# Inputs.net
KiCad netlist of a schematic drawn in Altium Designer
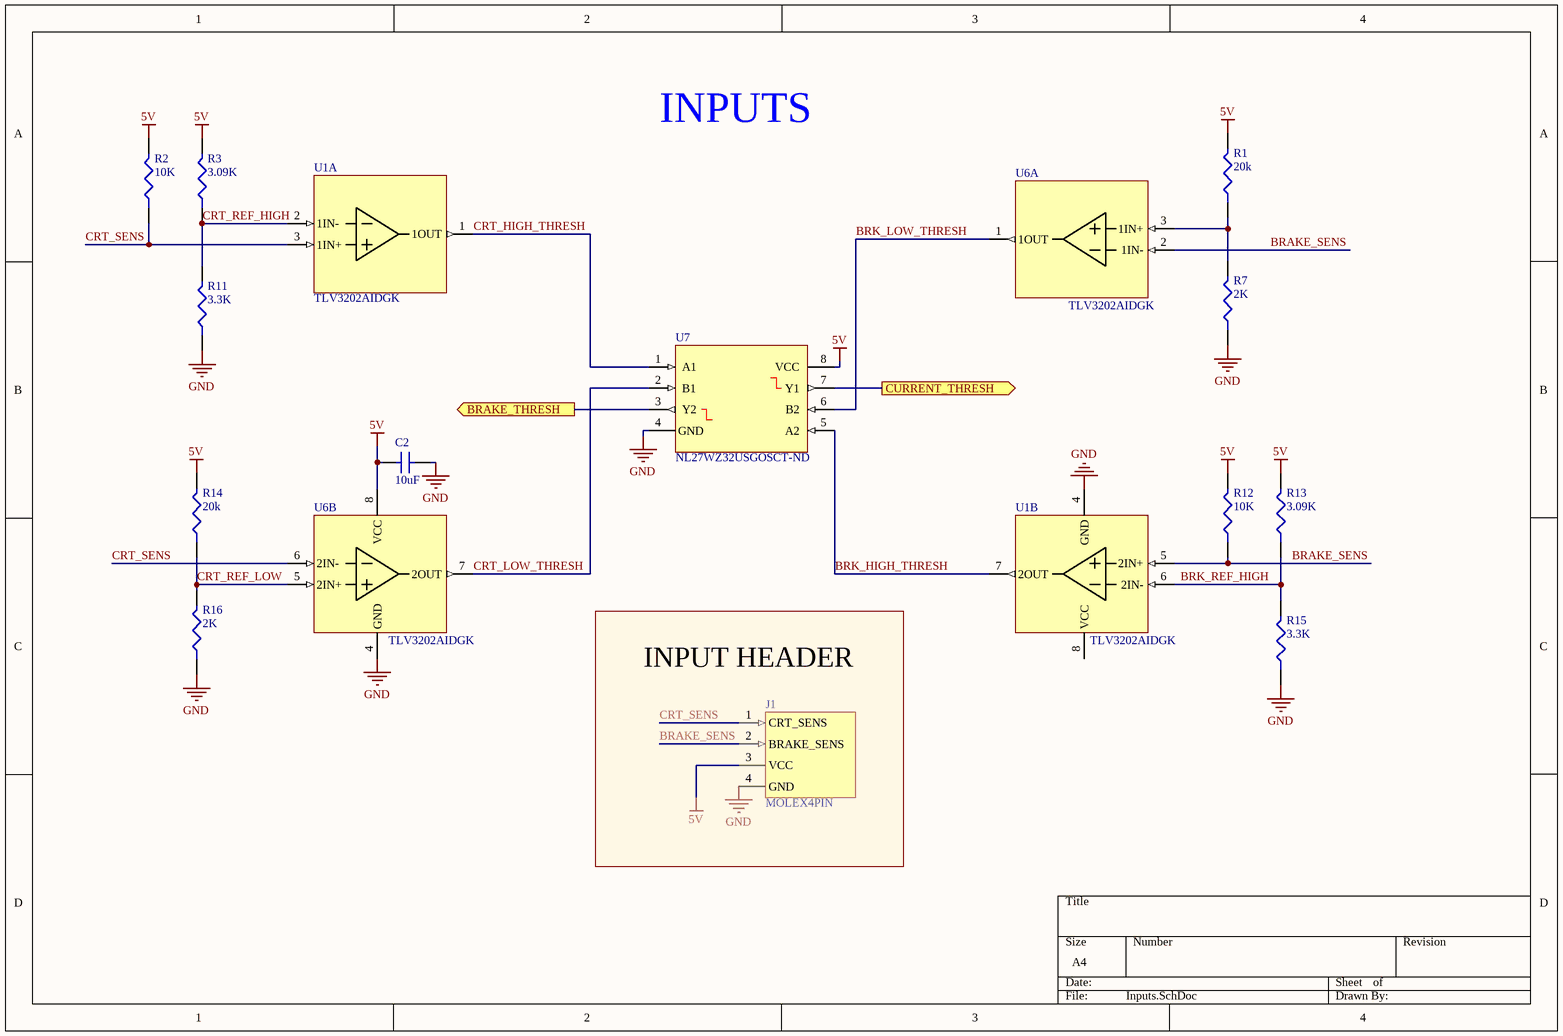
[diagram p0: Inputs.SchDoc]

(export (version "E")
  (design (tool "Eeschema 10.0.6"))
  (components
    (comp (ref "C2")
      (value "10uF")
      (footprint "C0805")
      (description "Cap Ceramic 10uF 10V X5R 10% SMD 0805 85C Embossed T/R")
      (fields
        (field (name "MANUFACTURER") "Samsung")
        (field (name "MANUFACTURER PART NUMBER") "CL21A106KPFNNNG")
      )
      (libsource (lib "BSPD") (part "CL21A106KPFNNNG"))
    )
    (comp (ref "J1")
      (value "MOLEX4PIN")
      (footprint "MOLEX_4PIN")
      (fields (field (name "MANUFACTURER") "Molex") (field (name "MANUFACTURER PART NUMBER") "43650-0400"))
      (libsource (lib "BSPD") (part "43650-0400"))
    )
    (comp (ref "R1")
      (value "20k")
      (footprint "RESC1608X06N")
      (fields
        (field (name "MANUFACTURER") "Yageo")
        (field (name "MANUFACTURER PART NUMBER") "RC0603FR-0722KL")
        (field (name "TOLERANCE") "1%")
      )
      (libsource (lib "BSPD") (part "RC0603FR-0722KL"))
    )
    (comp (ref "R2")
      (value "10K")
      (footprint "R0805")
      (description "RES SMD 10K OHM 0.1% 1/8W 0805")
      (fields
        (field (name "MANUFACTURER") "Panasonic")
        (field (name "MANUFACTURER PART NUMBER") "ERA6AEB103V")
      )
      (libsource (lib "BSPD") (part "ERA6AEB103V"))
    )
    (comp (ref "R3")
      (value "3.09K")
      (footprint "ERJPB3")
      (description "RES SMD 3.09K OHM 0.1% 1/5W 0603")
      (fields
        (field (name "MANUFACTURER") "Panasonic")
        (field (name "MANUFACTURER PART NUMBER") "ERJ-PB3B3091V")
      )
      (libsource (lib "BSPD") (part "ERJ-PB3B3091V"))
    )
    (comp (ref "R7")
      (value "2K")
      (footprint "R0805")
      (description "RES SMD 2K OHM 0.1% 1/8W 0805")
      (fields
        (field (name "MANUFACTURER") "Panasonic")
        (field (name "MANUFACTURER PART NUMBER") "ERA6AEB202V")
      )
      (libsource (lib "BSPD") (part "ERA6AEB202V"))
    )
    (comp (ref "R11")
      (value "3.3K")
      (footprint "ERJPB3")
      (description "RES SMD 3.3K OHM 0.1% 1/5W 0603")
      (fields
        (field (name "MANUFACTURER") "Panasonic")
        (field (name "MANUFACTURER PART NUMBER") "ERJ-PB3B3301V")
      )
      (libsource (lib "BSPD") (part "ERJ-PB3B3301V"))
    )
    (comp (ref "R12")
      (value "10K")
      (footprint "R0805")
      (description "RES SMD 10K OHM 0.1% 1/8W 0805")
      (fields
        (field (name "MANUFACTURER") "Panasonic")
        (field (name "MANUFACTURER PART NUMBER") "ERA6AEB103V")
      )
      (libsource (lib "BSPD") (part "ERA6AEB103V"))
    )
    (comp (ref "R13")
      (value "3.09K")
      (footprint "ERJPB3")
      (description "RES SMD 3.09K OHM 0.1% 1/5W 0603")
      (fields
        (field (name "MANUFACTURER") "Panasonic")
        (field (name "MANUFACTURER PART NUMBER") "ERJ-PB3B3091V")
      )
      (libsource (lib "BSPD") (part "ERJ-PB3B3091V"))
    )
    (comp (ref "R14")
      (value "20k")
      (footprint "RESC1608X06N")
      (fields
        (field (name "MANUFACTURER") "Yageo")
        (field (name "MANUFACTURER PART NUMBER") "RC0603FR-0722KL")
        (field (name "TOLERANCE") "1%")
      )
      (libsource (lib "BSPD") (part "RC0603FR-0722KL"))
    )
    (comp (ref "R15")
      (value "3.3K")
      (footprint "ERJPB3")
      (description "RES SMD 3.3K OHM 0.1% 1/5W 0603")
      (fields
        (field (name "MANUFACTURER") "Panasonic")
        (field (name "MANUFACTURER PART NUMBER") "ERJ-PB3B3301V")
      )
      (libsource (lib "BSPD") (part "ERJ-PB3B3301V"))
    )
    (comp (ref "R16")
      (value "2K")
      (footprint "R0805")
      (description "RES SMD 2K OHM 0.1% 1/8W 0805")
      (fields
        (field (name "MANUFACTURER") "Panasonic")
        (field (name "MANUFACTURER PART NUMBER") "ERA6AEB202V")
      )
      (libsource (lib "BSPD") (part "ERA6AEB202V"))
    )
    (comp (ref "U1")
      (value "TLV3202AIDGK")
      (footprint "TLV3202AIDGK")
      (description "IC COMPAR PWR RRI DL PP 8VSSOP")
      (fields (field (name "MANUFACTURER") "Texas Instruments"))
      (libsource (lib "") (part "TLV3202AIDGK_1"))
    )
    (comp (ref "U6")
      (value "TLV3202AIDGK")
      (footprint "TLV3202AIDGK")
      (description "IC COMPAR PWR RRI DL PP 8VSSOP")
      (fields (field (name "MANUFACTURER") "Texas Instruments"))
      (libsource (lib "") (part "TLV3202AIDGK_1"))
    )
    (comp (ref "U7")
      (value "NL27WZ32USGOSCT-ND")
      (footprint "TSSOP50P310X90-8N")
      (description "IC GATE OR 2CH 2-INP US8")
      (fields
        (field (name "MANUFACTURER") "ON Semiconductor")
        (field (name "MANUFACTURER PART NUMBER") "NL27WZ32USG")
      )
      (libsource (lib "BSPD") (part "OR GATE"))
    )
  )
  (nets
    (net (code "1") (name "/BRAKE_SENS") (class "Default")
      (node (ref "J1") (pin "2") (pinfunction "BRAKE_SENS_2") (pintype "input"))
      (node (ref "R12") (pin "1") (pinfunction "1_1") (pintype "passive"))
      (node (ref "U1") (pin "5") (pinfunction "2IN+_5") (pintype "input"))
      (node (ref "U6") (pin "2") (pinfunction "1IN-_2") (pintype "input"))
    )
    (net (code "2") (name "/BRAKE_THRESH") (class "Default")
      (node (ref "U7") (pin "3") (pinfunction "Y2_3") (pintype "output"))
    )
    (net (code "3") (name "/BRK_HIGH_THRESH") (class "Default")
      (node (ref "U1") (pin "7") (pinfunction "2OUT_7") (pintype "output"))
      (node (ref "U7") (pin "5") (pinfunction "A2_5") (pintype "input"))
    )
    (net (code "4") (name "/BRK_LOW_THRESH") (class "Default")
      (node (ref "U6") (pin "1") (pinfunction "1OUT_1") (pintype "output"))
      (node (ref "U7") (pin "6") (pinfunction "B2_6") (pintype "input"))
    )
    (net (code "5") (name "/BRK_REF_HIGH") (class "Default")
      (node (ref "R13") (pin "1") (pinfunction "1_1") (pintype "passive"))
      (node (ref "R15") (pin "2") (pinfunction "2_2") (pintype "passive"))
      (node (ref "U1") (pin "6") (pinfunction "2IN-_6") (pintype "input"))
    )
    (net (code "6") (name "/CRT_HIGH_THRESH") (class "Default")
      (node (ref "U1") (pin "1") (pinfunction "1OUT_1") (pintype "output"))
      (node (ref "U7") (pin "1") (pinfunction "A1_1") (pintype "input"))
    )
    (net (code "7") (name "/CRT_LOW_THRESH") (class "Default")
      (node (ref "U6") (pin "7") (pinfunction "2OUT_7") (pintype "output"))
      (node (ref "U7") (pin "2") (pinfunction "B1_2") (pintype "input"))
    )
    (net (code "8") (name "/CRT_REF_HIGH") (class "Default")
      (node (ref "R11") (pin "2") (pinfunction "2_2") (pintype "passive"))
      (node (ref "R3") (pin "1") (pinfunction "1_1") (pintype "passive"))
      (node (ref "U1") (pin "2") (pinfunction "1IN-_2") (pintype "input"))
    )
    (net (code "9") (name "/CRT_REF_LOW") (class "Default")
      (node (ref "R14") (pin "1") (pinfunction "1_1") (pintype "passive"))
      (node (ref "R16") (pin "2") (pinfunction "2_2") (pintype "passive"))
      (node (ref "U6") (pin "5") (pinfunction "2IN+_5") (pintype "input"))
    )
    (net (code "10") (name "/CRT_SENS") (class "Default")
      (node (ref "J1") (pin "1") (pinfunction "CRT_SENS_1") (pintype "input"))
      (node (ref "R2") (pin "1") (pinfunction "1_1") (pintype "passive"))
      (node (ref "U1") (pin "3") (pinfunction "1IN+_3") (pintype "input"))
      (node (ref "U6") (pin "6") (pinfunction "2IN-_6") (pintype "input"))
    )
    (net (code "11") (name "/CURRENT_THRESH") (class "Default")
      (node (ref "U7") (pin "7") (pinfunction "Y1_7") (pintype "output"))
    )
    (net (code "12") (name "5V") (class "Default")
      (node (ref "C2") (pin "2") (pinfunction "2_2") (pintype "passive"))
      (node (ref "J1") (pin "3") (pinfunction "VCC_3") (pintype "power_in"))
      (node (ref "R1") (pin "2") (pinfunction "2_2") (pintype "passive"))
      (node (ref "R12") (pin "2") (pinfunction "2_2") (pintype "passive"))
      (node (ref "R13") (pin "2") (pinfunction "2_2") (pintype "passive"))
      (node (ref "R14") (pin "2") (pinfunction "2_2") (pintype "passive"))
      (node (ref "R2") (pin "2") (pinfunction "2_2") (pintype "passive"))
      (node (ref "R3") (pin "2") (pinfunction "2_2") (pintype "passive"))
      (node (ref "U6") (pin "8") (pinfunction "VCC_8") (pintype "power_in"))
      (node (ref "U7") (pin "8") (pinfunction "VCC_8") (pintype "power_in"))
    )
    (net (code "13") (name "GND") (class "Default")
      (node (ref "C2") (pin "1") (pinfunction "1_1") (pintype "passive"))
      (node (ref "J1") (pin "4") (pinfunction "GND_4") (pintype "power_in"))
      (node (ref "R11") (pin "1") (pinfunction "1_1") (pintype "passive"))
      (node (ref "R15") (pin "1") (pinfunction "1_1") (pintype "passive"))
      (node (ref "R16") (pin "1") (pinfunction "1_1") (pintype "passive"))
      (node (ref "R7") (pin "1") (pinfunction "1_1") (pintype "passive"))
      (node (ref "U1") (pin "4") (pinfunction "GND_4") (pintype "power_in"))
      (node (ref "U6") (pin "4") (pinfunction "GND_4") (pintype "power_in"))
      (node (ref "U7") (pin "4") (pinfunction "GND_4") (pintype "power_in"))
    )
    (net (code "14") (name "Net-(U6A-1IN+)") (class "Default")
      (node (ref "R1") (pin "1") (pinfunction "1_1") (pintype "passive"))
      (node (ref "R7") (pin "2") (pinfunction "2_2") (pintype "passive"))
      (node (ref "U6") (pin "3") (pinfunction "1IN+_3") (pintype "input"))
    )
    (net (code "15") (name "unconnected-(U1B-VCC-Pad8)") (class "Default")
      (node (ref "U1") (pin "8") (pinfunction "VCC_8") (pintype "power_in"))
    )
  )
)
